# esp32_master_board.net
KiCad netlist of a schematic drawn in EAGLE
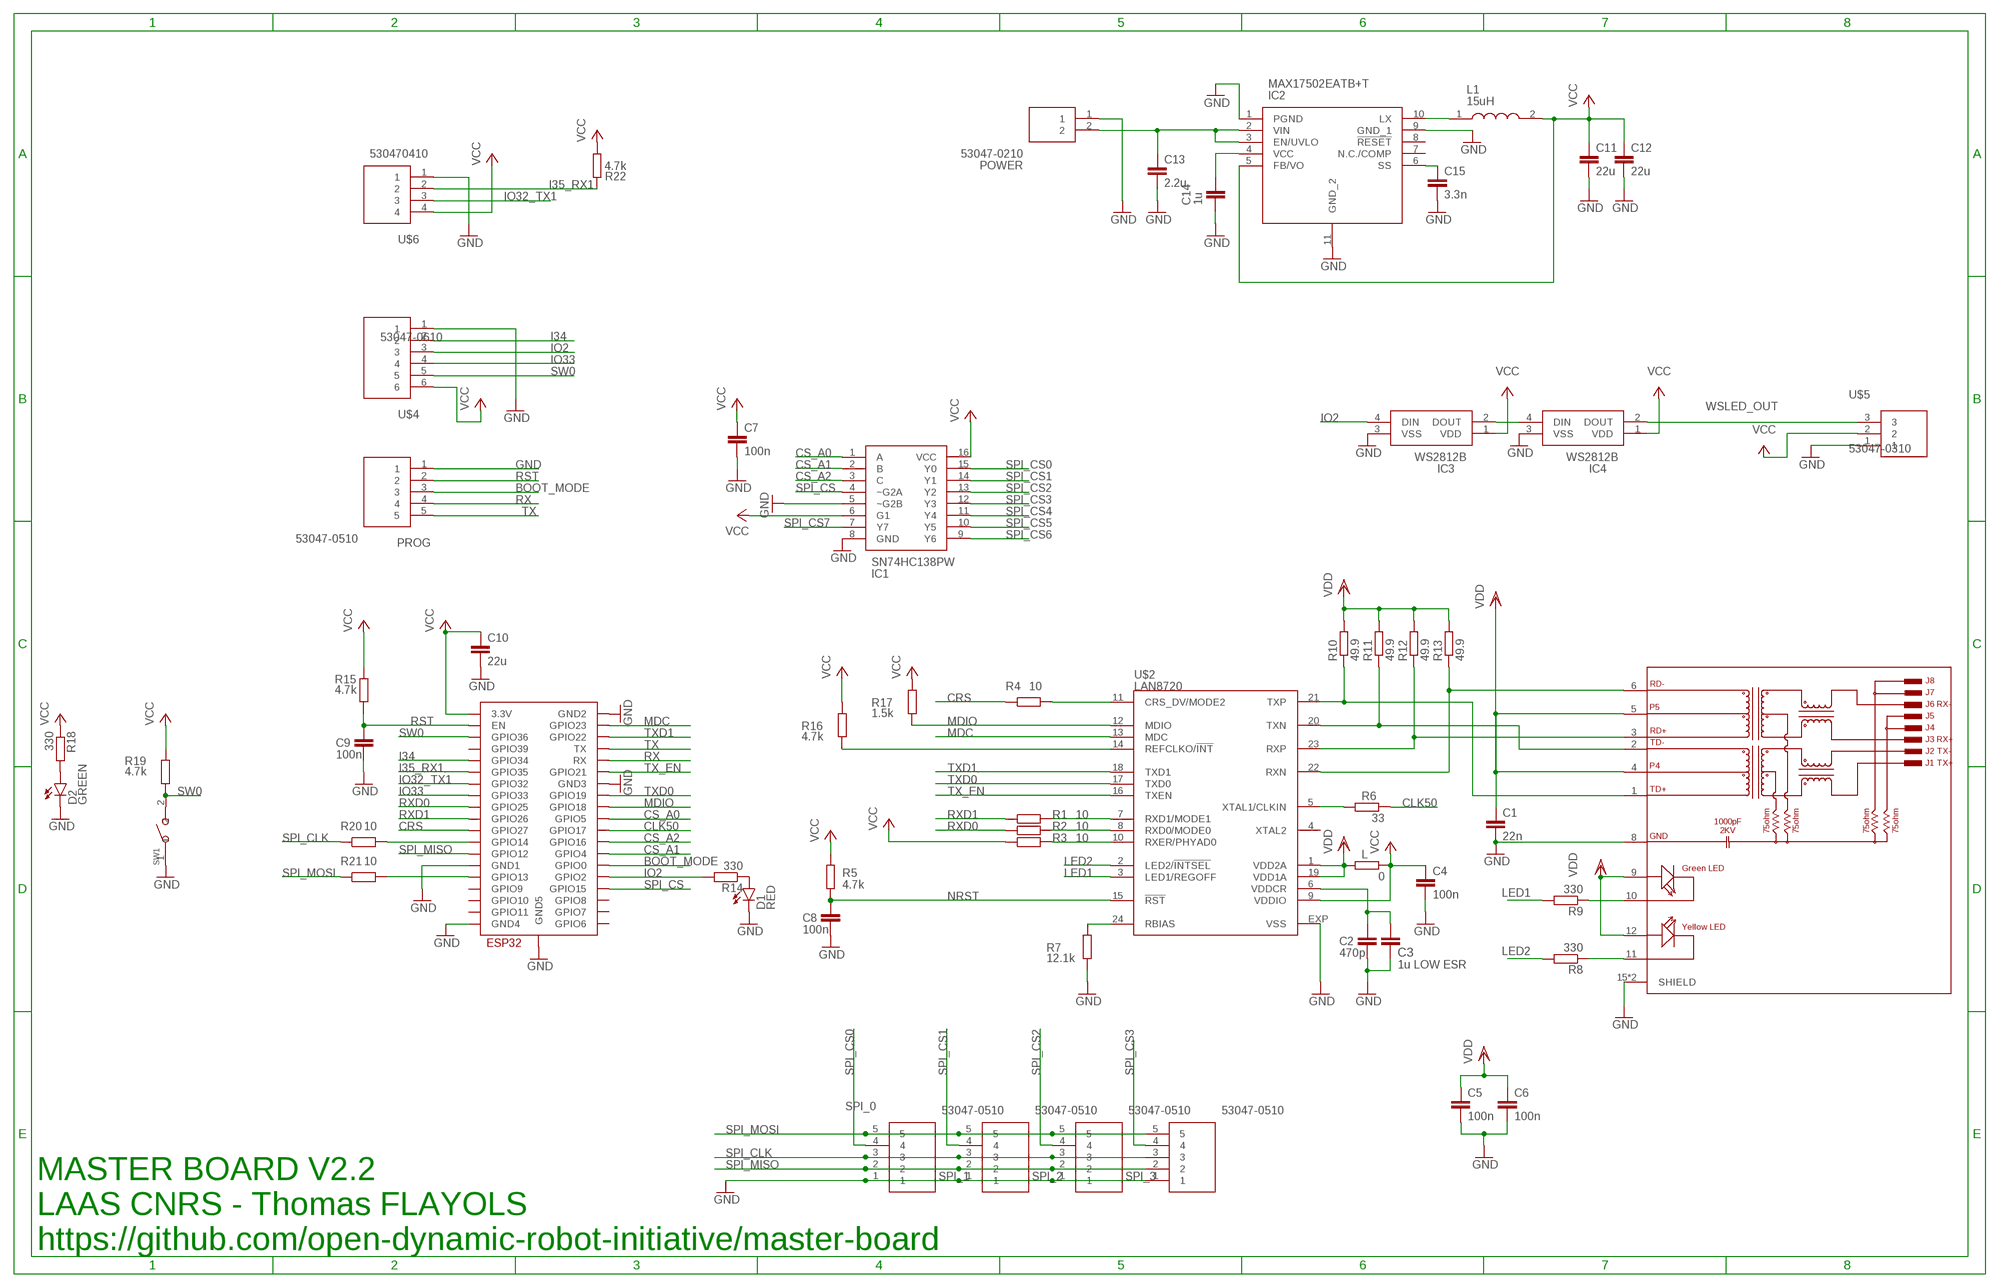
[diagram p0: schematic, sheet 1]

(export (version "E")
  (design (tool "Eeschema 10.0.6"))
  (components
    (comp (ref "C1")
      (value "22n")
      (footprint "eagle-import:0402")
      (fields (field (name "MANUFACTURER_PART_NUMBER") "885012205052"))
      (libsource (lib "eagle-import") (part "resistor_C-EUC0402"))
    )
    (comp (ref "C2")
      (value "470p")
      (footprint "eagle-import:0402")
      (fields (field (name "MANUFACTURER_PART_NUMBER") "CL05C471JB5NNNC"))
      (libsource (lib "eagle-import") (part "resistor_C-EUC0402"))
    )
    (comp (ref "C3")
      (value "1u LOW ESR")
      (footprint "eagle-import:0402")
      (fields (field (name "MANUFACTURER_PART_NUMBER") "CPL-CAP-X5R-0402-1UF-6.3V"))
      (libsource (lib "eagle-import") (part "resistor_C-EUC0402"))
    )
    (comp (ref "C4")
      (value "100n")
      (footprint "eagle-import:0402")
      (fields (field (name "MANUFACTURER_PART_NUMBER") "CPL-CAP-X7R-0402-100NF-16V"))
      (libsource (lib "eagle-import") (part "resistor_C-EUC0402"))
    )
    (comp (ref "C5")
      (value "100n")
      (footprint "eagle-import:0402")
      (fields (field (name "MANUFACTURER_PART_NUMBER") "CPL-CAP-X7R-0402-100NF-16V"))
      (libsource (lib "eagle-import") (part "resistor_C-EUC0402"))
    )
    (comp (ref "C6")
      (value "100n")
      (footprint "eagle-import:0402")
      (fields (field (name "MANUFACTURER_PART_NUMBER") "CPL-CAP-X7R-0402-100NF-16V"))
      (libsource (lib "eagle-import") (part "resistor_C-EUC0402"))
    )
    (comp (ref "C7")
      (value "100n")
      (footprint "eagle-import:0402")
      (fields (field (name "MANUFACTURER_PART_NUMBER") "CPL-CAP-X7R-0402-100NF-16V"))
      (libsource (lib "eagle-import") (part "resistor_C-EUC0402"))
    )
    (comp (ref "C8")
      (value "100n")
      (footprint "eagle-import:0402")
      (fields (field (name "MANUFACTURER_PART_NUMBER") "CPL-CAP-X7R-0402-100NF-16V"))
      (libsource (lib "eagle-import") (part "resistor_C-EUC0402"))
    )
    (comp (ref "C9")
      (value "100n")
      (footprint "eagle-import:0402")
      (fields (field (name "MANUFACTURER_PART_NUMBER") "CPL-CAP-X7R-0402-100NF-16V"))
      (libsource (lib "eagle-import") (part "resistor_C-EUC0402"))
    )
    (comp (ref "C10")
      (value "22u")
      (footprint "eagle-import:C0805")
      (fields (field (name "MANUFACTURER_PART_NUMBER") "CPL-CAP-X5R-0805-22UF-6.3V"))
      (libsource (lib "eagle-import") (part "C-EUC0805"))
    )
    (comp (ref "C11")
      (value "22u")
      (footprint "eagle-import:C0805")
      (fields (field (name "MANUFACTURER_PART_NUMBER") "CPL-CAP-X5R-0805-22UF-6.3V"))
      (libsource (lib "eagle-import") (part "C-EUC0805"))
    )
    (comp (ref "C12")
      (value "22u")
      (footprint "eagle-import:C0805")
      (fields (field (name "MANUFACTURER_PART_NUMBER") "CPL-CAP-X5R-0805-22UF-6.3V"))
      (libsource (lib "eagle-import") (part "C-EUC0805"))
    )
    (comp (ref "C13")
      (value "2.2u")
      (footprint "eagle-import:C1210")
      (fields (field (name "MANUFACTURER_PART_NUMBER") "C3225X7R1H225K250AB"))
      (libsource (lib "eagle-import") (part "resistor_C-EUC1210"))
    )
    (comp (ref "C14")
      (value "1u")
      (footprint "eagle-import:0402")
      (fields (field (name "MANUFACTURER_PART_NUMBER") "CPL-CAP-X5R-0402-1UF-6.3V"))
      (libsource (lib "eagle-import") (part "resistor_C-EUC0402"))
    )
    (comp (ref "C15")
      (value "3.3n")
      (footprint "eagle-import:0402")
      (fields (field (name "MANUFACTURER_PART_NUMBER") "885012205064"))
      (libsource (lib "eagle-import") (part "resistor_C-EUC0402"))
    )
    (comp (ref "D1")
      (value "RED")
      (footprint "eagle-import:CHIPLED_0603")
      (fields (field (name "MANUFACTURER_PART_NUMBER") "CPL-LED-0603-RED"))
      (libsource (lib "eagle-import") (part "LEDCHIPLED_0603"))
    )
    (comp (ref "D2")
      (value "GREEN")
      (footprint "eagle-import:CHIPLED_0603")
      (fields (field (name "MANUFACTURER_PART_NUMBER") "CPL-LED-0603-GREEN"))
      (libsource (lib "eagle-import") (part "LEDCHIPLED_0603"))
    )
    (comp (ref "IC1")
      (value "SN74HC138PW")
      (footprint "eagle-import:SOP65P640X120-16N")
      (fields (field (name "RS_PART_NUMBER") "6631928"))
      (libsource (lib "eagle-import") (part "SN74HC138PW"))
    )
    (comp (ref "IC2")
      (value "MAX17502EATB+T")
      (footprint "eagle-import:SON50P200X300X80-11N")
      (fields (field (name "MOUSER_PART_NUMBER") "700-MAX17502EATB+T"))
      (libsource (lib "eagle-import") (part "MAX17502EATB+T"))
    )
    (comp (ref "IC3")
      (value "WS2812B")
      (footprint "eagle-import:WS2812B")
      (libsource (lib "eagle-import") (part "WS2812B"))
    )
    (comp (ref "IC4")
      (value "WS2812B")
      (footprint "eagle-import:WS2812B")
      (libsource (lib "eagle-import") (part "WS2812B"))
    )
    (comp (ref "L")
      (value "0")
      (footprint "eagle-import:0402")
      (fields (field (name "MANUFACTURER_PART_NUMBER") "CPL-RES-0402-0-0.063W"))
      (libsource (lib "eagle-import") (part "R-EU_R0402"))
    )
    (comp (ref "L1")
      (value "15uH")
      (footprint "eagle-import:LPS6235")
      (fields
        (field (name "MANUFACTURER_PART_NUMBER") "LPS6235-153MRB")
        (field (name "MOUSER_PART_NUMBER") "994-LPS6235-153MRB")
      )
      (libsource (lib "eagle-import") (part "LPS6235-153MRB"))
    )
    (comp (ref "POWER")
      (value "53047-0210")
      (footprint "eagle-import:530470210")
      (fields
        (field (name "MOUSER_PART_NUMBER") "538-53047-0210")
        (field (name "MANUFACTURER_PART_NUMBER") "DF13-3P-1.25DSA")
      )
      (libsource (lib "eagle-import") (part "53047-0210"))
    )
    (comp (ref "PROG")
      (value "53047-0510")
      (footprint "eagle-import:530470510")
      (fields
        (field (name "MOUSER_PART_NUMBER") "538-53047-0510")
        (field (name "MANUFACTURER_PART_NUMBER") "DF13-5P-1.25DSA")
      )
      (libsource (lib "eagle-import") (part "53047-0510"))
    )
    (comp (ref "R1")
      (value "10")
      (footprint "eagle-import:0402")
      (fields (field (name "MANUFACTURER_PART_NUMBER") "CPL-RES-0402-10-0.063W"))
      (libsource (lib "eagle-import") (part "R-EU_R0402"))
    )
    (comp (ref "R2")
      (value "10")
      (footprint "eagle-import:0402")
      (fields (field (name "MANUFACTURER_PART_NUMBER") "CPL-RES-0402-10-0.063W"))
      (libsource (lib "eagle-import") (part "R-EU_R0402"))
    )
    (comp (ref "R3")
      (value "10")
      (footprint "eagle-import:0402")
      (fields (field (name "MANUFACTURER_PART_NUMBER") "CPL-RES-0402-10-0.063W"))
      (libsource (lib "eagle-import") (part "R-EU_R0402"))
    )
    (comp (ref "R4")
      (value "10")
      (footprint "eagle-import:0402")
      (fields (field (name "MANUFACTURER_PART_NUMBER") "CPL-RES-0402-10-0.063W"))
      (libsource (lib "eagle-import") (part "R-EU_R0402"))
    )
    (comp (ref "R5")
      (value "4.7k")
      (footprint "eagle-import:0402")
      (fields (field (name "MANUFACTURER_PART_NUMBER") "CPL-RES-0402-4.7K-0.063W"))
      (libsource (lib "eagle-import") (part "R-EU_R0402"))
    )
    (comp (ref "R6")
      (value "33")
      (footprint "eagle-import:0402")
      (fields (field (name "MANUFACTURER_PART_NUMBER") "CRCW040233R0FKEDC"))
      (libsource (lib "eagle-import") (part "R-EU_R0402"))
    )
    (comp (ref "R7")
      (value "12.1k")
      (footprint "eagle-import:0402")
      (fields (field (name "MANUFACTURER_PART_NUMBER") "ERJ-U02F1212X"))
      (libsource (lib "eagle-import") (part "R-EU_R0402"))
    )
    (comp (ref "R8")
      (value "330")
      (footprint "eagle-import:0402")
      (fields (field (name "MANUFACTURER_PART_NUMBER") "RC0402JR-13330RL"))
      (libsource (lib "eagle-import") (part "R-EU_R0402"))
    )
    (comp (ref "R9")
      (value "330")
      (footprint "eagle-import:0402")
      (fields (field (name "MANUFACTURER_PART_NUMBER") "RC0402JR-13330RL"))
      (libsource (lib "eagle-import") (part "R-EU_R0402"))
    )
    (comp (ref "R10")
      (value "49.9")
      (footprint "eagle-import:0402")
      (fields (field (name "MANUFACTURER_PART_NUMBER") "CRCW040249R9FKEDC"))
      (libsource (lib "eagle-import") (part "R-EU_R0402"))
    )
    (comp (ref "R11")
      (value "49.9")
      (footprint "eagle-import:0402")
      (fields (field (name "MANUFACTURER_PART_NUMBER") "CRCW040249R9FKEDC"))
      (libsource (lib "eagle-import") (part "R-EU_R0402"))
    )
    (comp (ref "R12")
      (value "49.9")
      (footprint "eagle-import:0402")
      (fields (field (name "MANUFACTURER_PART_NUMBER") "CRCW040249R9FKEDC"))
      (libsource (lib "eagle-import") (part "R-EU_R0402"))
    )
    (comp (ref "R13")
      (value "49.9")
      (footprint "eagle-import:0402")
      (fields (field (name "MANUFACTURER_PART_NUMBER") "CRCW040249R9FKEDC"))
      (libsource (lib "eagle-import") (part "R-EU_R0402"))
    )
    (comp (ref "R14")
      (value "330")
      (footprint "eagle-import:0402")
      (fields (field (name "MANUFACTURER_PART_NUMBER") "RC0402JR-13330RL"))
      (libsource (lib "eagle-import") (part "R-EU_R0402"))
    )
    (comp (ref "R15")
      (value "4.7k")
      (footprint "eagle-import:0402")
      (fields (field (name "MANUFACTURER_PART_NUMBER") "CPL-RES-0402-4.7K-0.063W"))
      (libsource (lib "eagle-import") (part "R-EU_R0402"))
    )
    (comp (ref "R16")
      (value "4.7k")
      (footprint "eagle-import:0402")
      (fields (field (name "MANUFACTURER_PART_NUMBER") "CPL-RES-0402-4.7K-0.063W"))
      (libsource (lib "eagle-import") (part "R-EU_R0402"))
    )
    (comp (ref "R17")
      (value "1.5k")
      (footprint "eagle-import:0402")
      (fields (field (name "MANUFACTURER_PART_NUMBER") "ERJ2GEJ152X"))
      (libsource (lib "eagle-import") (part "R-EU_R0402"))
    )
    (comp (ref "R18")
      (value "330")
      (footprint "eagle-import:0402")
      (fields (field (name "MANUFACTURER_PART_NUMBER") "RC0402JR-13330RL"))
      (libsource (lib "eagle-import") (part "R-EU_R0402"))
    )
    (comp (ref "R19")
      (value "4.7k")
      (footprint "eagle-import:0402")
      (fields (field (name "MANUFACTURER_PART_NUMBER") "CPL-RES-0402-4.7K-0.063W"))
      (libsource (lib "eagle-import") (part "R-EU_R0402"))
    )
    (comp (ref "R20")
      (value "10")
      (footprint "eagle-import:0402")
      (fields (field (name "MANUFACTURER_PART_NUMBER") "CPL-RES-0402-10-0.063W"))
      (libsource (lib "eagle-import") (part "R-EU_R0402"))
    )
    (comp (ref "R21")
      (value "10")
      (footprint "eagle-import:0402")
      (fields (field (name "MANUFACTURER_PART_NUMBER") "CPL-RES-0402-10-0.063W"))
      (libsource (lib "eagle-import") (part "R-EU_R0402"))
    )
    (comp (ref "R22")
      (value "4.7k")
      (footprint "eagle-import:0402")
      (fields (field (name "MANUFACTURER_PART_NUMBER") "CPL-RES-0402-4.7K-0.063W"))
      (libsource (lib "eagle-import") (part "R-EU_R0402"))
    )
    (comp (ref "SPI_0")
      (value "53047-0510")
      (footprint "eagle-import:530470510")
      (fields
        (field (name "MOUSER_PART_NUMBER") "538-53047-0510")
        (field (name "MANUFACTURER_PART_NUMBER") "DF13-5P-1.25DSA")
      )
      (libsource (lib "eagle-import") (part "53047-0510"))
    )
    (comp (ref "SPI_1")
      (value "53047-0510")
      (footprint "eagle-import:530470510")
      (fields
        (field (name "MOUSER_PART_NUMBER") "538-53047-0510")
        (field (name "MANUFACTURER_PART_NUMBER") "DF13-5P-1.25DSA")
      )
      (libsource (lib "eagle-import") (part "53047-0510"))
    )
    (comp (ref "SPI_2")
      (value "53047-0510")
      (footprint "eagle-import:530470510")
      (fields
        (field (name "MOUSER_PART_NUMBER") "538-53047-0510")
        (field (name "MANUFACTURER_PART_NUMBER") "DF13-5P-1.25DSA")
      )
      (libsource (lib "eagle-import") (part "53047-0510"))
    )
    (comp (ref "SPI_3")
      (value "53047-0510")
      (footprint "eagle-import:530470510")
      (fields
        (field (name "MOUSER_PART_NUMBER") "538-53047-0510")
        (field (name "MANUFACTURER_PART_NUMBER") "DF13-5P-1.25DSA")
      )
      (libsource (lib "eagle-import") (part "53047-0510"))
    )
    (comp (ref "SW1")
      (value "B3U-1000P-2P-SMD")
      (footprint "eagle-import:SW2-2.6-3.0X2.5X1.2+0.4MM")
      (fields (field (name "MANUFACTURER_PART_NUMBER") "B3U-1000P"))
      (libsource (lib "eagle-import") (part "SMD-BUTTON(2P-3.0X2.5X1.2+0.4MM)-B3U-1000P-2P-SMD"))
    )
    (comp (ref "U$1")
      (value "ESP32-WROOM")
      (footprint "eagle-import:ESP32-WROOM")
      (fields (field (name "MANUFACTURER_PART_NUMBER") "ESP32-WROOM-32D"))
      (libsource (lib "eagle-import") (part "ESP32-WROOM"))
    )
    (comp (ref "U$2")
      (value "LAN8720")
      (footprint "eagle-import:QFN24")
      (fields (field (name "MANUFACTURER_PART_NUMBER") "LAN8720A-CP"))
      (libsource (lib "eagle-import") (part "LAN8720"))
    )
    (comp (ref "U$3")
      (value "HR911105A")
      (footprint "eagle-import:HANRUN_HR911105A")
      (fields (field (name "MF") "DFRobot"))
      (libsource (lib "eagle-import") (part "HR911105A"))
    )
    (comp (ref "U$4")
      (value "53047-0610")
      (footprint "eagle-import:530470610")
      (fields
        (field (name "MOUSER_PART_NUMBER") "538-53047-0610")
        (field (name "MANUFACTURER_PART_NUMBER") "DF13-6P-1.25DSA")
      )
      (libsource (lib "eagle-import") (part "53047-0610"))
    )
    (comp (ref "U$5")
      (value "53047-0310")
      (footprint "eagle-import:530470310")
      (fields
        (field (name "MOUSER_PART_NUMBER") "538-53047-0310")
        (field (name "MANUFACTURER_PART_NUMBER") "DF13-3P-1.25DSA")
      )
      (libsource (lib "eagle-import") (part "53047-0310"))
    )
    (comp (ref "U$6")
      (value "530470410")
      (footprint "eagle-import:530470410")
      (fields (field (name "MANUFACTURER_PART_NUMBER") "DF13-4P-1.25DSA"))
      (libsource (lib "eagle-import") (part "530470410"))
    )
  )
  (nets
    (net (code "1") (name "/BOOT_MODE") (class "Default")
      (node (ref "PROG") (pin "3") (pinfunction "3_3") (pintype "bidirectional"))
      (node (ref "U$1") (pin "IO0") (pinfunction "GPIO0_IO0") (pintype "bidirectional"))
    )
    (net (code "2") (name "/CLK50") (class "Default")
      (node (ref "R6") (pin "1") (pinfunction "1_1") (pintype "passive"))
      (node (ref "U$1") (pin "IO17") (pinfunction "GPIO17_IO17") (pintype "bidirectional"))
    )
    (net (code "3") (name "/CRS") (class "Default")
      (node (ref "R4") (pin "1") (pinfunction "1_1") (pintype "passive"))
      (node (ref "U$1") (pin "IO27") (pinfunction "GPIO27_IO27") (pintype "bidirectional"))
    )
    (net (code "4") (name "/CS_A0") (class "Default")
      (node (ref "IC1") (pin "1") (pinfunction "A_1") (pintype "bidirectional"))
      (node (ref "U$1") (pin "IO5") (pinfunction "GPIO5_IO5") (pintype "bidirectional"))
    )
    (net (code "5") (name "/CS_A1") (class "Default")
      (node (ref "IC1") (pin "2") (pinfunction "B_2") (pintype "bidirectional"))
      (node (ref "U$1") (pin "IO4") (pinfunction "GPIO4_IO4") (pintype "bidirectional"))
    )
    (net (code "6") (name "/CS_A2") (class "Default")
      (node (ref "IC1") (pin "3") (pinfunction "C_3") (pintype "bidirectional"))
      (node (ref "U$1") (pin "IO16") (pinfunction "GPIO16_IO16") (pintype "bidirectional"))
    )
    (net (code "7") (name "/I34") (class "Default")
      (node (ref "U$1") (pin "IO34") (pinfunction "GPIO34_IO34") (pintype "bidirectional"))
      (node (ref "U$4") (pin "2") (pinfunction "2_2") (pintype "bidirectional"))
    )
    (net (code "8") (name "/I35_RX1") (class "Default")
      (node (ref "R22") (pin "2") (pinfunction "2_2") (pintype "passive"))
      (node (ref "U$1") (pin "IO35") (pinfunction "GPIO35_IO35") (pintype "bidirectional"))
      (node (ref "U$6") (pin "2") (pinfunction "2_2") (pintype "bidirectional"))
    )
    (net (code "9") (name "/IO2") (class "Default")
      (node (ref "IC3") (pin "4") (pinfunction "DIN_4") (pintype "input"))
      (node (ref "R14") (pin "2") (pinfunction "2_2") (pintype "passive"))
      (node (ref "U$1") (pin "IO2") (pinfunction "GPIO2_IO2") (pintype "bidirectional"))
      (node (ref "U$4") (pin "3") (pinfunction "3_3") (pintype "bidirectional"))
    )
    (net (code "10") (name "/IO32_TX1") (class "Default")
      (node (ref "U$1") (pin "IO32") (pinfunction "GPIO32_IO32") (pintype "bidirectional"))
      (node (ref "U$6") (pin "3") (pinfunction "3_3") (pintype "bidirectional"))
    )
    (net (code "11") (name "/IO33") (class "Default")
      (node (ref "U$1") (pin "IO33") (pinfunction "GPIO33_IO33") (pintype "bidirectional"))
      (node (ref "U$4") (pin "4") (pinfunction "4_4") (pintype "bidirectional"))
    )
    (net (code "12") (name "/LED1") (class "Default")
      (node (ref "R9") (pin "2") (pinfunction "2_2") (pintype "passive"))
      (node (ref "U$2") (pin "3") (pinfunction "LED1/REGOFF_3") (pintype "bidirectional"))
    )
    (net (code "13") (name "/LED2") (class "Default")
      (node (ref "R8") (pin "2") (pinfunction "2_2") (pintype "passive"))
      (node (ref "U$2") (pin "2") (pinfunction "LED2/~{INTSEL}_2") (pintype "bidirectional"))
    )
    (net (code "14") (name "/MDC") (class "Default")
      (node (ref "U$1") (pin "IO23") (pinfunction "GPIO23_IO23") (pintype "bidirectional"))
      (node (ref "U$2") (pin "13") (pinfunction "MDC_13") (pintype "bidirectional"))
    )
    (net (code "15") (name "/MDIO") (class "Default")
      (node (ref "R17") (pin "1") (pinfunction "1_1") (pintype "passive"))
      (node (ref "U$1") (pin "IO18") (pinfunction "GPIO18_IO18") (pintype "bidirectional"))
      (node (ref "U$2") (pin "12") (pinfunction "MDIO_12") (pintype "bidirectional"))
    )
    (net (code "16") (name "/NRST") (class "Default")
      (node (ref "C8") (pin "1") (pinfunction "1_1") (pintype "passive"))
      (node (ref "R5") (pin "1") (pinfunction "1_1") (pintype "passive"))
      (node (ref "U$2") (pin "15") (pinfunction "~{RST}_15") (pintype "bidirectional"))
    )
    (net (code "17") (name "/RST") (class "Default")
      (node (ref "C9") (pin "1") (pinfunction "1_1") (pintype "passive"))
      (node (ref "PROG") (pin "2") (pinfunction "2_2") (pintype "bidirectional"))
      (node (ref "R15") (pin "1") (pinfunction "1_1") (pintype "passive"))
      (node (ref "U$1") (pin "EN") (pinfunction "EN_EN") (pintype "bidirectional"))
    )
    (net (code "18") (name "/RX") (class "Default")
      (node (ref "PROG") (pin "4") (pinfunction "4_4") (pintype "bidirectional"))
      (node (ref "U$1") (pin "RX") (pinfunction "RX_RX") (pintype "bidirectional"))
    )
    (net (code "19") (name "/RXD0") (class "Default")
      (node (ref "R2") (pin "1") (pinfunction "1_1") (pintype "passive"))
      (node (ref "U$1") (pin "IO25") (pinfunction "GPIO25_IO25") (pintype "bidirectional"))
    )
    (net (code "20") (name "/RXD1") (class "Default")
      (node (ref "R1") (pin "1") (pinfunction "1_1") (pintype "passive"))
      (node (ref "U$1") (pin "IO26") (pinfunction "GPIO26_IO26") (pintype "bidirectional"))
    )
    (net (code "21") (name "/SPI_CLK") (class "Default")
      (node (ref "R20") (pin "1") (pinfunction "1_1") (pintype "passive"))
      (node (ref "SPI_0") (pin "3") (pinfunction "3_3") (pintype "bidirectional"))
      (node (ref "SPI_1") (pin "3") (pinfunction "3_3") (pintype "bidirectional"))
      (node (ref "SPI_2") (pin "3") (pinfunction "3_3") (pintype "bidirectional"))
      (node (ref "SPI_3") (pin "3") (pinfunction "3_3") (pintype "bidirectional"))
    )
    (net (code "22") (name "/SPI_CS") (class "Default")
      (node (ref "IC1") (pin "4") (pinfunction "~{G2A}_4") (pintype "bidirectional"))
      (node (ref "U$1") (pin "IO15") (pinfunction "GPIO15_IO15") (pintype "bidirectional"))
    )
    (net (code "23") (name "/SPI_CS0") (class "Default")
      (node (ref "IC1") (pin "15") (pinfunction "Y0_15") (pintype "bidirectional"))
      (node (ref "SPI_0") (pin "4") (pinfunction "4_4") (pintype "bidirectional"))
    )
    (net (code "24") (name "/SPI_CS1") (class "Default")
      (node (ref "IC1") (pin "14") (pinfunction "Y1_14") (pintype "bidirectional"))
      (node (ref "SPI_1") (pin "4") (pinfunction "4_4") (pintype "bidirectional"))
    )
    (net (code "25") (name "/SPI_CS2") (class "Default")
      (node (ref "IC1") (pin "13") (pinfunction "Y2_13") (pintype "bidirectional"))
      (node (ref "SPI_2") (pin "4") (pinfunction "4_4") (pintype "bidirectional"))
    )
    (net (code "26") (name "/SPI_CS3") (class "Default")
      (node (ref "IC1") (pin "12") (pinfunction "Y3_12") (pintype "bidirectional"))
      (node (ref "SPI_3") (pin "4") (pinfunction "4_4") (pintype "bidirectional"))
    )
    (net (code "27") (name "/SPI_CS4") (class "Default")
      (node (ref "IC1") (pin "11") (pinfunction "Y4_11") (pintype "bidirectional"))
    )
    (net (code "28") (name "/SPI_CS5") (class "Default")
      (node (ref "IC1") (pin "10") (pinfunction "Y5_10") (pintype "bidirectional"))
    )
    (net (code "29") (name "/SPI_CS6") (class "Default")
      (node (ref "IC1") (pin "9") (pinfunction "Y6_9") (pintype "bidirectional"))
    )
    (net (code "30") (name "/SPI_CS7") (class "Default")
      (node (ref "IC1") (pin "7") (pinfunction "Y7_7") (pintype "bidirectional"))
    )
    (net (code "31") (name "/SPI_MISO") (class "Default")
      (node (ref "SPI_0") (pin "2") (pinfunction "2_2") (pintype "bidirectional"))
      (node (ref "SPI_1") (pin "2") (pinfunction "2_2") (pintype "bidirectional"))
      (node (ref "SPI_2") (pin "2") (pinfunction "2_2") (pintype "bidirectional"))
      (node (ref "SPI_3") (pin "2") (pinfunction "2_2") (pintype "bidirectional"))
      (node (ref "U$1") (pin "IO12") (pinfunction "GPIO12_IO12") (pintype "bidirectional"))
    )
    (net (code "32") (name "/SPI_MOSI") (class "Default")
      (node (ref "R21") (pin "1") (pinfunction "1_1") (pintype "passive"))
      (node (ref "SPI_0") (pin "5") (pinfunction "5_5") (pintype "bidirectional"))
      (node (ref "SPI_1") (pin "5") (pinfunction "5_5") (pintype "bidirectional"))
      (node (ref "SPI_2") (pin "5") (pinfunction "5_5") (pintype "bidirectional"))
      (node (ref "SPI_3") (pin "5") (pinfunction "5_5") (pintype "bidirectional"))
    )
    (net (code "33") (name "/SW0") (class "Default")
      (node (ref "R19") (pin "1") (pinfunction "1_1") (pintype "passive"))
      (node (ref "SW1") (pin "2") (pinfunction "2_2") (pintype "bidirectional"))
      (node (ref "U$1") (pin "SENSOR_VP") (pinfunction "GPIO36_SENSOR_VP") (pintype "bidirectional"))
      (node (ref "U$4") (pin "5") (pinfunction "5_5") (pintype "bidirectional"))
    )
    (net (code "34") (name "/TX") (class "Default")
      (node (ref "PROG") (pin "5") (pinfunction "5_5") (pintype "bidirectional"))
      (node (ref "U$1") (pin "TX") (pinfunction "TX_TX") (pintype "bidirectional"))
    )
    (net (code "35") (name "/TXD0") (class "Default")
      (node (ref "U$1") (pin "IO19") (pinfunction "GPIO19_IO19") (pintype "bidirectional"))
      (node (ref "U$2") (pin "17") (pinfunction "TXD0_17") (pintype "bidirectional"))
    )
    (net (code "36") (name "/TXD1") (class "Default")
      (node (ref "U$1") (pin "IO22") (pinfunction "GPIO22_IO22") (pintype "bidirectional"))
      (node (ref "U$2") (pin "18") (pinfunction "TXD1_18") (pintype "bidirectional"))
    )
    (net (code "37") (name "/TX_EN") (class "Default")
      (node (ref "U$1") (pin "IO21") (pinfunction "GPIO21_IO21") (pintype "bidirectional"))
      (node (ref "U$2") (pin "16") (pinfunction "TXEN_16") (pintype "bidirectional"))
    )
    (net (code "38") (name "/WSLED_OUT") (class "Default")
      (node (ref "IC4") (pin "2") (pinfunction "DOUT_2") (pintype "output"))
      (node (ref "U$5") (pin "3") (pinfunction "3_3") (pintype "bidirectional"))
    )
    (net (code "39") (name "GND") (class "Default")
      (node (ref "C1") (pin "2") (pinfunction "2_2") (pintype "passive"))
      (node (ref "C10") (pin "2") (pinfunction "2_2") (pintype "passive"))
      (node (ref "C11") (pin "2") (pinfunction "2_2") (pintype "passive"))
      (node (ref "C12") (pin "2") (pinfunction "2_2") (pintype "passive"))
      (node (ref "C13") (pin "2") (pinfunction "2_2") (pintype "passive"))
      (node (ref "C14") (pin "1") (pinfunction "1_1") (pintype "passive"))
      (node (ref "C15") (pin "2") (pinfunction "2_2") (pintype "passive"))
      (node (ref "C2") (pin "2") (pinfunction "2_2") (pintype "passive"))
      (node (ref "C3") (pin "2") (pinfunction "2_2") (pintype "passive"))
      (node (ref "C4") (pin "2") (pinfunction "2_2") (pintype "passive"))
      (node (ref "C5") (pin "2") (pinfunction "2_2") (pintype "passive"))
      (node (ref "C6") (pin "2") (pinfunction "2_2") (pintype "passive"))
      (node (ref "C7") (pin "2") (pinfunction "2_2") (pintype "passive"))
      (node (ref "C8") (pin "2") (pinfunction "2_2") (pintype "passive"))
      (node (ref "C9") (pin "2") (pinfunction "2_2") (pintype "passive"))
      (node (ref "D1") (pin "C") (pinfunction "C_C") (pintype "passive"))
      (node (ref "D2") (pin "C") (pinfunction "C_C") (pintype "passive"))
      (node (ref "IC1") (pin "5") (pinfunction "~{G2B}_5") (pintype "bidirectional"))
      (node (ref "IC1") (pin "8") (pinfunction "GND_8") (pintype "bidirectional"))
      (node (ref "IC2") (pin "1") (pinfunction "PGND_1") (pintype "bidirectional"))
      (node (ref "IC2") (pin "11") (pinfunction "GND_2_11") (pintype "bidirectional"))
      (node (ref "IC2") (pin "9") (pinfunction "GND_1_9") (pintype "bidirectional"))
      (node (ref "IC3") (pin "3") (pinfunction "VSS_3") (pintype "power_in"))
      (node (ref "IC4") (pin "3") (pinfunction "VSS_3") (pintype "power_in"))
      (node (ref "POWER") (pin "1") (pinfunction "1_1") (pintype "bidirectional"))
      (node (ref "PROG") (pin "1") (pinfunction "1_1") (pintype "bidirectional"))
      (node (ref "R7") (pin "1") (pinfunction "1_1") (pintype "passive"))
      (node (ref "SPI_0") (pin "1") (pinfunction "1_1") (pintype "bidirectional"))
      (node (ref "SPI_1") (pin "1") (pinfunction "1_1") (pintype "bidirectional"))
      (node (ref "SPI_2") (pin "1") (pinfunction "1_1") (pintype "bidirectional"))
      (node (ref "SPI_3") (pin "1") (pinfunction "1_1") (pintype "bidirectional"))
      (node (ref "SW1") (pin "1") (pinfunction "1_1") (pintype "bidirectional"))
      (node (ref "U$1") (pin "GND1") (pinfunction "GND1_GND1") (pintype "bidirectional"))
      (node (ref "U$1") (pin "GND2") (pinfunction "GND2_GND2") (pintype "bidirectional"))
      (node (ref "U$1") (pin "GND3") (pinfunction "GND3_GND3") (pintype "bidirectional"))
      (node (ref "U$1") (pin "GND4") (pinfunction "GND4_GND4") (pintype "bidirectional"))
      (node (ref "U$1") (pin "GND5") (pinfunction "GND5_GND5") (pintype "bidirectional"))
      (node (ref "U$2") (pin "EXP") (pinfunction "VSS_EXP") (pintype "power_in"))
      (node (ref "U$3") (pin "15") (pinfunction "SHIELD_15") (pintype "passive"))
      (node (ref "U$3") (pin "16") (pinfunction "SHIELD_16") (pintype "passive"))
      (node (ref "U$3") (pin "8") (pinfunction "GND_8") (pintype "power_in"))
      (node (ref "U$4") (pin "1") (pinfunction "1_1") (pintype "bidirectional"))
      (node (ref "U$5") (pin "1") (pinfunction "1_1") (pintype "bidirectional"))
      (node (ref "U$6") (pin "1") (pinfunction "1_1") (pintype "bidirectional"))
    )
    (net (code "40") (name "Net-(D1-PadA)") (class "Default")
      (node (ref "D1") (pin "A") (pinfunction "A_A") (pintype "passive"))
      (node (ref "R14") (pin "1") (pinfunction "1_1") (pintype "passive"))
    )
    (net (code "41") (name "Net-(D2-PadA)") (class "Default")
      (node (ref "D2") (pin "A") (pinfunction "A_A") (pintype "passive"))
      (node (ref "R18") (pin "2") (pinfunction "2_2") (pintype "passive"))
    )
    (net (code "42") (name "Net-(IC2-EN{slash}UVLO)") (class "Default")
      (node (ref "C13") (pin "1") (pinfunction "1_1") (pintype "passive"))
      (node (ref "IC2") (pin "2") (pinfunction "VIN_2") (pintype "bidirectional"))
      (node (ref "IC2") (pin "3") (pinfunction "EN/UVLO_3") (pintype "bidirectional"))
      (node (ref "POWER") (pin "2") (pinfunction "2_2") (pintype "bidirectional"))
    )
    (net (code "43") (name "Net-(IC2-LX)") (class "Default")
      (node (ref "IC2") (pin "10") (pinfunction "LX_10") (pintype "bidirectional"))
      (node (ref "L1") (pin "1") (pinfunction "1_1") (pintype "bidirectional"))
    )
    (net (code "44") (name "Net-(IC2-SS)") (class "Default")
      (node (ref "C15") (pin "1") (pinfunction "1_1") (pintype "passive"))
      (node (ref "IC2") (pin "6") (pinfunction "SS_6") (pintype "bidirectional"))
    )
    (net (code "45") (name "Net-(IC2-VCC)") (class "Default")
      (node (ref "C14") (pin "2") (pinfunction "2_2") (pintype "passive"))
      (node (ref "IC2") (pin "4") (pinfunction "VCC_4") (pintype "bidirectional"))
    )
    (net (code "46") (name "Net-(IC3-DOUT)") (class "Default")
      (node (ref "IC3") (pin "2") (pinfunction "DOUT_2") (pintype "output"))
      (node (ref "IC4") (pin "4") (pinfunction "DIN_4") (pintype "input"))
    )
    (net (code "47") (name "Net-(U$1-GPIO13)") (class "Default")
      (node (ref "R21") (pin "2") (pinfunction "2_2") (pintype "passive"))
      (node (ref "U$1") (pin "IO13") (pinfunction "GPIO13_IO13") (pintype "bidirectional"))
    )
    (net (code "48") (name "Net-(U$1-GPIO14)") (class "Default")
      (node (ref "R20") (pin "2") (pinfunction "2_2") (pintype "passive"))
      (node (ref "U$1") (pin "IO14") (pinfunction "GPIO14_IO14") (pintype "bidirectional"))
    )
    (net (code "49") (name "Net-(U$2-CRS_DV{slash}MODE2)") (class "Default")
      (node (ref "R4") (pin "2") (pinfunction "2_2") (pintype "passive"))
      (node (ref "U$2") (pin "11") (pinfunction "CRS_DV/MODE2_11") (pintype "bidirectional"))
    )
    (net (code "50") (name "Net-(U$2-RBIAS)") (class "Default")
      (node (ref "R7") (pin "2") (pinfunction "2_2") (pintype "passive"))
      (node (ref "U$2") (pin "24") (pinfunction "RBIAS_24") (pintype "bidirectional"))
    )
    (net (code "51") (name "Net-(U$2-REFCLKO{slash}~{INT})") (class "Default")
      (node (ref "R16") (pin "1") (pinfunction "1_1") (pintype "passive"))
      (node (ref "U$2") (pin "14") (pinfunction "REFCLKO/~{INT}_14") (pintype "bidirectional"))
    )
    (net (code "52") (name "Net-(U$2-RXD0{slash}MODE0)") (class "Default")
      (node (ref "R2") (pin "2") (pinfunction "2_2") (pintype "passive"))
      (node (ref "U$2") (pin "8") (pinfunction "RXD0/MODE0_8") (pintype "bidirectional"))
    )
    (net (code "53") (name "Net-(U$2-RXD1{slash}MODE1)") (class "Default")
      (node (ref "R1") (pin "2") (pinfunction "2_2") (pintype "passive"))
      (node (ref "U$2") (pin "7") (pinfunction "RXD1/MODE1_7") (pintype "bidirectional"))
    )
    (net (code "54") (name "Net-(U$2-RXER{slash}PHYAD0)") (class "Default")
      (node (ref "R3") (pin "2") (pinfunction "2_2") (pintype "passive"))
      (node (ref "U$2") (pin "10") (pinfunction "RXER/PHYAD0_10") (pintype "bidirectional"))
    )
    (net (code "55") (name "Net-(U$2-RXN)") (class "Default")
      (node (ref "R13") (pin "1") (pinfunction "1_1") (pintype "passive"))
      (node (ref "U$2") (pin "22") (pinfunction "RXN_22") (pintype "bidirectional"))
      (node (ref "U$3") (pin "6") (pinfunction "RD-_6") (pintype "passive"))
    )
    (net (code "56") (name "Net-(U$2-RXP)") (class "Default")
      (node (ref "R12") (pin "1") (pinfunction "1_1") (pintype "passive"))
      (node (ref "U$2") (pin "23") (pinfunction "RXP_23") (pintype "bidirectional"))
      (node (ref "U$3") (pin "3") (pinfunction "RD+_3") (pintype "passive"))
    )
    (net (code "57") (name "Net-(U$2-TXN)") (class "Default")
      (node (ref "R11") (pin "1") (pinfunction "1_1") (pintype "passive"))
      (node (ref "U$2") (pin "20") (pinfunction "TXN_20") (pintype "bidirectional"))
      (node (ref "U$3") (pin "2") (pinfunction "TD-_2") (pintype "passive"))
    )
    (net (code "58") (name "Net-(U$2-TXP)") (class "Default")
      (node (ref "R10") (pin "1") (pinfunction "1_1") (pintype "passive"))
      (node (ref "U$2") (pin "21") (pinfunction "TXP_21") (pintype "bidirectional"))
      (node (ref "U$3") (pin "1") (pinfunction "TD+_1") (pintype "passive"))
    )
    (net (code "59") (name "Net-(U$2-VDDCR)") (class "Default")
      (node (ref "C2") (pin "1") (pinfunction "1_1") (pintype "passive"))
      (node (ref "C3") (pin "1") (pinfunction "1_1") (pintype "passive"))
      (node (ref "U$2") (pin "6") (pinfunction "VDDCR_6") (pintype "power_in"))
    )
    (net (code "60") (name "Net-(U$2-XTAL1{slash}CLKIN)") (class "Default")
      (node (ref "R6") (pin "2") (pinfunction "2_2") (pintype "passive"))
      (node (ref "U$2") (pin "5") (pinfunction "XTAL1/CLKIN_5") (pintype "bidirectional"))
    )
    (net (code "61") (name "Net-(U$3-GC)") (class "Default")
      (node (ref "R9") (pin "1") (pinfunction "1_1") (pintype "passive"))
      (node (ref "U$3") (pin "10") (pinfunction "GC_10") (pintype "passive"))
    )
    (net (code "62") (name "Net-(U$3-YC)") (class "Default")
      (node (ref "R8") (pin "1") (pinfunction "1_1") (pintype "passive"))
      (node (ref "U$3") (pin "11") (pinfunction "YC_11") (pintype "passive"))
    )
    (net (code "63") (name "VCC") (class "Default")
      (node (ref "C10") (pin "1") (pinfunction "1_1") (pintype "passive"))
      (node (ref "C11") (pin "1") (pinfunction "1_1") (pintype "passive"))
      (node (ref "C12") (pin "1") (pinfunction "1_1") (pintype "passive"))
      (node (ref "C4") (pin "1") (pinfunction "1_1") (pintype "passive"))
      (node (ref "C7") (pin "1") (pinfunction "1_1") (pintype "passive"))
      (node (ref "IC1") (pin "16") (pinfunction "VCC_16") (pintype "bidirectional"))
      (node (ref "IC1") (pin "6") (pinfunction "G1_6") (pintype "bidirectional"))
      (node (ref "IC2") (pin "5") (pinfunction "FB/VO_5") (pintype "bidirectional"))
      (node (ref "IC3") (pin "1") (pinfunction "VDD_1") (pintype "power_in"))
      (node (ref "IC4") (pin "1") (pinfunction "VDD_1") (pintype "power_in"))
      (node (ref "L") (pin "1") (pinfunction "1_1") (pintype "passive"))
      (node (ref "L1") (pin "2") (pinfunction "2_2") (pintype "bidirectional"))
      (node (ref "R15") (pin "2") (pinfunction "2_2") (pintype "passive"))
      (node (ref "R16") (pin "2") (pinfunction "2_2") (pintype "passive"))
      (node (ref "R17") (pin "2") (pinfunction "2_2") (pintype "passive"))
      (node (ref "R18") (pin "1") (pinfunction "1_1") (pintype "passive"))
      (node (ref "R19") (pin "2") (pinfunction "2_2") (pintype "passive"))
      (node (ref "R22") (pin "1") (pinfunction "1_1") (pintype "passive"))
      (node (ref "R3") (pin "1") (pinfunction "1_1") (pintype "passive"))
      (node (ref "R5") (pin "2") (pinfunction "2_2") (pintype "passive"))
      (node (ref "U$1") (pin "3V3") (pinfunction "3.3V_3V3") (pintype "bidirectional"))
      (node (ref "U$2") (pin "9") (pinfunction "VDDIO_9") (pintype "power_in"))
      (node (ref "U$4") (pin "6") (pinfunction "6_6") (pintype "bidirectional"))
      (node (ref "U$5") (pin "2") (pinfunction "2_2") (pintype "bidirectional"))
      (node (ref "U$6") (pin "4") (pinfunction "4_4") (pintype "bidirectional"))
    )
    (net (code "64") (name "VDD") (class "Default")
      (node (ref "C1") (pin "1") (pinfunction "1_1") (pintype "passive"))
      (node (ref "C5") (pin "1") (pinfunction "1_1") (pintype "passive"))
      (node (ref "C6") (pin "1") (pinfunction "1_1") (pintype "passive"))
      (node (ref "L") (pin "2") (pinfunction "2_2") (pintype "passive"))
      (node (ref "R10") (pin "2") (pinfunction "2_2") (pintype "passive"))
      (node (ref "R11") (pin "2") (pinfunction "2_2") (pintype "passive"))
      (node (ref "R12") (pin "2") (pinfunction "2_2") (pintype "passive"))
      (node (ref "R13") (pin "2") (pinfunction "2_2") (pintype "passive"))
      (node (ref "U$2") (pin "1") (pinfunction "VDD2A_1") (pintype "power_in"))
      (node (ref "U$2") (pin "19") (pinfunction "VDD1A_19") (pintype "power_in"))
      (node (ref "U$3") (pin "12") (pinfunction "YA_12") (pintype "passive"))
      (node (ref "U$3") (pin "4") (pinfunction "P4_4") (pintype "passive"))
      (node (ref "U$3") (pin "5") (pinfunction "P5_5") (pintype "passive"))
      (node (ref "U$3") (pin "9") (pinfunction "GA_9") (pintype "passive"))
    )
    (net (code "65") (name "unconnected-(IC2-N.C.{slash}COMP-Pad7)") (class "Default")
      (node (ref "IC2") (pin "7") (pinfunction "N.C./COMP_7") (pintype "bidirectional"))
    )
    (net (code "66") (name "unconnected-(IC2-~{RESET}-Pad8)") (class "Default")
      (node (ref "IC2") (pin "8") (pinfunction "~{RESET}_8") (pintype "bidirectional"))
    )
    (net (code "67") (name "unconnected-(U$1-GPIO6-PadCLK)") (class "Default")
      (node (ref "U$1") (pin "CLK") (pinfunction "GPIO6_CLK") (pintype "bidirectional"))
    )
    (net (code "68") (name "unconnected-(U$1-GPIO7-PadSD0)") (class "Default")
      (node (ref "U$1") (pin "SD0") (pinfunction "GPIO7_SD0") (pintype "bidirectional"))
    )
    (net (code "69") (name "unconnected-(U$1-GPIO8-PadSD1)") (class "Default")
      (node (ref "U$1") (pin "SD1") (pinfunction "GPIO8_SD1") (pintype "bidirectional"))
    )
    (net (code "70") (name "unconnected-(U$1-GPIO9-PadSD2)") (class "Default")
      (node (ref "U$1") (pin "SD2") (pinfunction "GPIO9_SD2") (pintype "bidirectional"))
    )
    (net (code "71") (name "unconnected-(U$1-GPIO10-PadSD3)") (class "Default")
      (node (ref "U$1") (pin "SD3") (pinfunction "GPIO10_SD3") (pintype "bidirectional"))
    )
    (net (code "72") (name "unconnected-(U$1-GPIO11-PadCMD)") (class "Default")
      (node (ref "U$1") (pin "CMD") (pinfunction "GPIO11_CMD") (pintype "bidirectional"))
    )
    (net (code "73") (name "unconnected-(U$1-GPIO39-PadSENSOR_VN)") (class "Default")
      (node (ref "U$1") (pin "SENSOR_VN") (pinfunction "GPIO39_SENSOR_VN") (pintype "bidirectional"))
    )
    (net (code "74") (name "unconnected-(U$2-XTAL2-Pad4)") (class "Default")
      (node (ref "U$2") (pin "4") (pinfunction "XTAL2_4") (pintype "bidirectional"))
    )
  )
)
